# usb_breakout_rev_2.net
KiCad netlist of a schematic drawn in Altium Designer
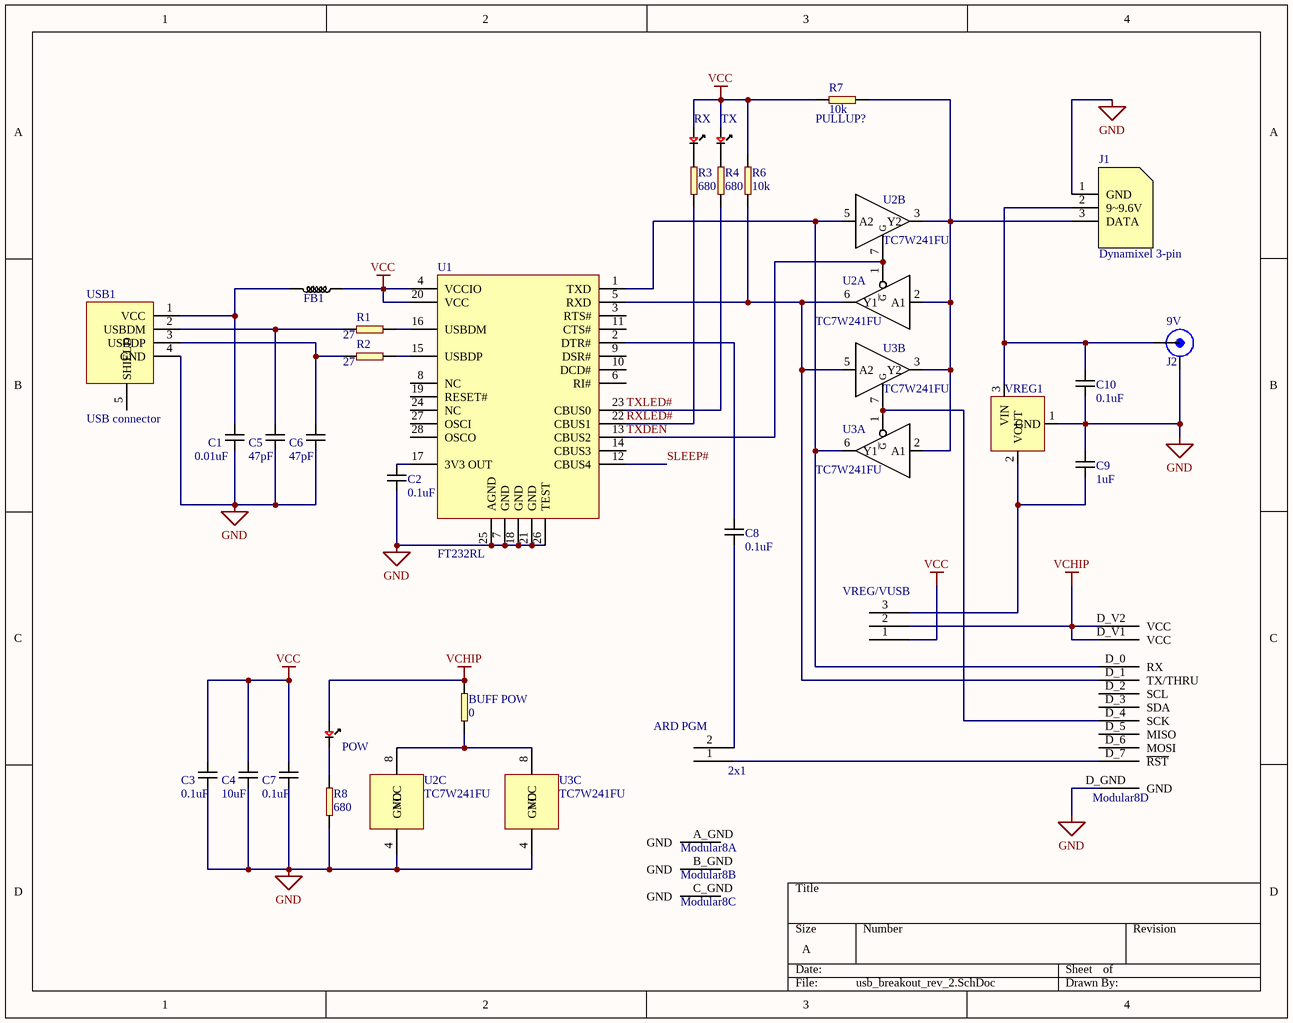
[diagram p0: usb_breakout_rev_2.SchDoc]

(export (version "E")
  (design (tool "Eeschema 10.0.6"))
  (components
    (comp (ref "ARD PGM")
      (value "2x1")
      (footprint "2x1 THRU HOLES 0.1\" PITCH")
      (libsource (lib "OpBots") (part "2x1"))
    )
    (comp (ref "BUFF POW")
      (value "R 0")
      (footprint "0603")
      (fields (field (name "R") "0"))
      (libsource (lib "RLC") (part "R 0"))
    )
    (comp (ref "C1")
      (value "C 0.01uF 25V")
      (footprint "0603")
      (fields (field (name "C") "0.01uF"))
      (libsource (lib "RLC") (part "C 0.01uF 25V"))
    )
    (comp (ref "C2")
      (value "C 0.1uF 25V")
      (footprint "0603")
      (fields (field (name "C") "0.1uF"))
      (libsource (lib "RLC") (part "C 0.1uF 25V"))
    )
    (comp (ref "C3")
      (value "C 0.1uF 25V")
      (footprint "0603")
      (fields (field (name "C") "0.1uF"))
      (libsource (lib "RLC") (part "C 0.1uF 25V"))
    )
    (comp (ref "C4")
      (value "C 10uF 25V")
      (footprint "0603")
      (fields (field (name "C") "10uF"))
      (libsource (lib "RLC") (part "C 10uF 25V"))
    )
    (comp (ref "C5")
      (value "C 47pF 50V")
      (footprint "0603")
      (fields (field (name "C") "47pF"))
      (libsource (lib "RLC") (part "C 47pF 50V"))
    )
    (comp (ref "C6")
      (value "C 47pF 50V")
      (footprint "0603")
      (fields (field (name "C") "47pF"))
      (libsource (lib "RLC") (part "C 47pF 50V"))
    )
    (comp (ref "C7")
      (value "C 0.1uF 25V")
      (footprint "0603")
      (fields (field (name "C") "0.1uF"))
      (libsource (lib "RLC") (part "C 0.1uF 25V"))
    )
    (comp (ref "C8")
      (value "C 0.1uF 25V")
      (footprint "0603")
      (fields (field (name "C") "0.1uF"))
      (libsource (lib "RLC") (part "C 0.1uF 25V"))
    )
    (comp (ref "C9")
      (value "C 1uF 25V")
      (footprint "0603")
      (fields (field (name "C") "1uF"))
      (libsource (lib "RLC") (part "C 1uF 25V"))
    )
    (comp (ref "C10")
      (value "C 0.1uF 25V")
      (footprint "0603")
      (fields (field (name "C") "0.1uF"))
      (libsource (lib "RLC") (part "C 0.1uF 25V"))
    )
    (comp (ref "FB1")
      (value "L Ferrite Bead 600ohm")
      (footprint "0603")
      (libsource (lib "RLC") (part "L Ferrite Bead 600ohm"))
    )
    (comp (ref "J1")
      (value "Dynamixel 3-pin")
      (footprint "DYNAMIXEL 3-PIN")
      (libsource (lib "OpBots") (part "Dynamixel 3-pin"))
    )
    (comp (ref "J2")
      (value "9V")
      (footprint "DC JACK 2.1MM SMT")
      (libsource (lib "OpBots") (part "SMT 2.1MM DC JACK"))
    )
    (comp (ref "Modular8")
      (value "modular8_rev2_D")
      (footprint "modular8 edge D flipped")
      (libsource (lib "OpBots") (part "modular8_rev2_D"))
    )
    (comp (ref "POW") (value "LEDG") (footprint "0805 - LED") (libsource (lib "OpBots") (part "LEDG")))
    (comp (ref "R1")
      (value "R 27")
      (footprint "0603")
      (fields (field (name "R") "27"))
      (libsource (lib "RLC") (part "R 27"))
    )
    (comp (ref "R2")
      (value "R 27")
      (footprint "0603")
      (fields (field (name "R") "27"))
      (libsource (lib "RLC") (part "R 27"))
    )
    (comp (ref "R3")
      (value "R 680")
      (footprint "0603")
      (fields (field (name "R") "680"))
      (libsource (lib "RLC") (part "R 680"))
    )
    (comp (ref "R4")
      (value "R 680")
      (footprint "0603")
      (fields (field (name "R") "680"))
      (libsource (lib "RLC") (part "R 680"))
    )
    (comp (ref "R6")
      (value "R 10k")
      (footprint "0603")
      (fields (field (name "R") "10k"))
      (libsource (lib "RLC") (part "R 10k"))
    )
    (comp (ref "R7")
      (value "PULLUP?")
      (footprint "0603")
      (fields (field (name "R") "10k"))
      (libsource (lib "") (part "R 10k_1"))
    )
    (comp (ref "R8")
      (value "R 680")
      (footprint "0603")
      (fields (field (name "R") "680"))
      (libsource (lib "RLC") (part "R 680"))
    )
    (comp (ref "RX") (value "LEDY") (footprint "0805 - LED") (libsource (lib "OpBots") (part "LEDY")))
    (comp (ref "TX") (value "LEDY") (footprint "0805 - LED") (libsource (lib "OpBots") (part "LEDY")))
    (comp (ref "U1") (value "FT232RL") (footprint "SSOP28") (libsource (lib "OpBots") (part "FT232RL")))
    (comp (ref "U2") (value "TC7W241FU") (footprint "MSOP8") (libsource (lib "") (part "TC7W241FU_1")))
    (comp (ref "U3") (value "TC7W241FU") (footprint "MSOP8") (libsource (lib "") (part "TC7W241FU_1")))
    (comp (ref "USB1")
      (value "USB connector")
      (footprint "USB MINI")
      (libsource (lib "OpBots") (part "USB connector"))
    )
    (comp (ref "VREG/VUSB")
      (value "3x1")
      (footprint "3x1 THRU HOLES 0.1\" PITCH")
      (libsource (lib "OpBots") (part "3x1"))
    )
    (comp (ref "VREG1")
      (value "MCP1754ST 5V REG")
      (footprint "SOT-23-3")
      (libsource (lib "OpBots") (part "MCP1754ST 5V REG"))
    )
  )
  (nets
    (net (code "1") (name "/RXLED#") (class "Default")
      (node (ref "R3") (pin "2") (pintype "passive"))
      (node (ref "U1") (pin "22") (pinfunction "CBUS1_22") (pintype "passive"))
    )
    (net (code "2") (name "/SLEEP#") (class "Default")
      (node (ref "U1") (pin "12") (pinfunction "CBUS4_12") (pintype "passive"))
    )
    (net (code "3") (name "/TXDEN") (class "Default")
      (node (ref "U1") (pin "13") (pinfunction "CBUS2_13") (pintype "passive"))
      (node (ref "U2") (pin "1") (pinfunction "~{G}_1") (pintype "passive"))
      (node (ref "U2") (pin "7") (pinfunction "G_7") (pintype "passive"))
    )
    (net (code "4") (name "/TXLED#") (class "Default")
      (node (ref "R4") (pin "2") (pintype "passive"))
      (node (ref "U1") (pin "23") (pinfunction "CBUS0_23") (pintype "passive"))
    )
    (net (code "5") (name "GND") (class "Default")
      (node (ref "C1") (pin "2") (pintype "passive"))
      (node (ref "C10") (pin "2") (pintype "passive"))
      (node (ref "C2") (pin "2") (pintype "passive"))
      (node (ref "C3") (pin "2") (pintype "passive"))
      (node (ref "C4") (pin "2") (pintype "passive"))
      (node (ref "C5") (pin "2") (pintype "passive"))
      (node (ref "C6") (pin "2") (pintype "passive"))
      (node (ref "C7") (pin "2") (pintype "passive"))
      (node (ref "C9") (pin "1") (pintype "passive"))
      (node (ref "J1") (pin "1") (pinfunction "GND_1") (pintype "passive"))
      (node (ref "J2") (pin "2") (pinfunction "G_2") (pintype "passive"))
      (node (ref "Modular8") (pin "D_GND") (pinfunction "GND_D_GND") (pintype "passive"))
      (node (ref "R8") (pin "2") (pintype "passive"))
      (node (ref "U1") (pin "18") (pinfunction "GND_18") (pintype "passive"))
      (node (ref "U1") (pin "21") (pinfunction "GND_21") (pintype "passive"))
      (node (ref "U1") (pin "25") (pinfunction "AGND_25") (pintype "passive"))
      (node (ref "U1") (pin "26") (pinfunction "TEST_26") (pintype "passive"))
      (node (ref "U1") (pin "7") (pinfunction "GND_7") (pintype "passive"))
      (node (ref "U2") (pin "4") (pinfunction "GND_4") (pintype "passive"))
      (node (ref "U3") (pin "4") (pinfunction "GND_4") (pintype "passive"))
      (node (ref "USB1") (pin "4") (pinfunction "GND_4") (pintype "passive"))
      (node (ref "VREG1") (pin "1") (pinfunction "GND_1") (pintype "passive"))
    )
    (net (code "6") (name "Net-(ARD PGM-Pad2)") (class "Default")
      (node (ref "ARD PGM") (pin "2") (pintype "passive"))
      (node (ref "C8") (pin "2") (pintype "passive"))
    )
    (net (code "7") (name "Net-(J1-9~9.6V)") (class "Default")
      (node (ref "C10") (pin "1") (pintype "passive"))
      (node (ref "J1") (pin "2") (pinfunction "9~9.6V_2") (pintype "passive"))
      (node (ref "J2") (pin "1") (pinfunction "S_1") (pintype "passive"))
      (node (ref "VREG1") (pin "3") (pinfunction "VIN_3") (pintype "passive"))
    )
    (net (code "8") (name "Net-(J1-DATA)") (class "Default")
      (node (ref "J1") (pin "3") (pinfunction "DATA_3") (pintype "passive"))
      (node (ref "R7") (pin "2") (pintype "passive"))
      (node (ref "U2") (pin "2") (pinfunction "A1_2") (pintype "passive"))
      (node (ref "U2") (pin "3") (pinfunction "Y2_3") (pintype "passive"))
      (node (ref "U3") (pin "2") (pinfunction "A1_2") (pintype "passive"))
      (node (ref "U3") (pin "3") (pinfunction "Y2_3") (pintype "passive"))
    )
    (net (code "9") (name "Net-(Modular8D-RX)") (class "Default")
      (node (ref "Modular8") (pin "D_0") (pinfunction "RX_D_0") (pintype "passive"))
      (node (ref "U1") (pin "1") (pinfunction "TXD_1") (pintype "passive"))
      (node (ref "U2") (pin "5") (pinfunction "A2_5") (pintype "passive"))
      (node (ref "U3") (pin "6") (pinfunction "Y1_6") (pintype "passive"))
    )
    (net (code "10") (name "Net-(Modular8D-SCK)") (class "Default")
      (node (ref "Modular8") (pin "D_4") (pinfunction "SCK_D_4") (pintype "passive"))
      (node (ref "U3") (pin "1") (pinfunction "~{G}_1") (pintype "passive"))
      (node (ref "U3") (pin "7") (pinfunction "G_7") (pintype "passive"))
    )
    (net (code "11") (name "Net-(Modular8D-TX{slash}THRU)") (class "Default")
      (node (ref "Modular8") (pin "D_1") (pinfunction "TX/THRU_D_1") (pintype "passive"))
      (node (ref "R6") (pin "2") (pintype "passive"))
      (node (ref "U1") (pin "5") (pinfunction "RXD_5") (pintype "passive"))
      (node (ref "U2") (pin "6") (pinfunction "Y1_6") (pintype "passive"))
      (node (ref "U3") (pin "5") (pinfunction "A2_5") (pintype "passive"))
    )
    (net (code "12") (name "Net-(Modular8D-~{RST})") (class "Default")
      (node (ref "ARD PGM") (pin "1") (pintype "passive"))
      (node (ref "Modular8") (pin "D_7") (pinfunction "~{RST}_D_7") (pintype "passive"))
    )
    (net (code "13") (name "Net-(POW-K)") (class "Default")
      (node (ref "POW") (pin "2") (pinfunction "K_2") (pintype "passive"))
      (node (ref "R8") (pin "1") (pintype "passive"))
    )
    (net (code "14") (name "Net-(RX-K)") (class "Default")
      (node (ref "R3") (pin "1") (pintype "passive"))
      (node (ref "RX") (pin "2") (pinfunction "K_2") (pintype "passive"))
    )
    (net (code "15") (name "Net-(TX-K)") (class "Default")
      (node (ref "R4") (pin "1") (pintype "passive"))
      (node (ref "TX") (pin "2") (pinfunction "K_2") (pintype "passive"))
    )
    (net (code "16") (name "Net-(U1-3V3_OUT)") (class "Default")
      (node (ref "C2") (pin "1") (pintype "passive"))
      (node (ref "U1") (pin "17") (pinfunction "3V3_OUT_17") (pintype "passive"))
    )
    (net (code "17") (name "Net-(U1-DTR#)") (class "Default")
      (node (ref "C8") (pin "1") (pintype "passive"))
      (node (ref "U1") (pin "2") (pinfunction "DTR#_2") (pintype "passive"))
    )
    (net (code "18") (name "Net-(U1-USBDM)") (class "Default")
      (node (ref "R1") (pin "2") (pintype "passive"))
      (node (ref "U1") (pin "16") (pinfunction "USBDM_16") (pintype "passive"))
    )
    (net (code "19") (name "Net-(U1-USBDP)") (class "Default")
      (node (ref "R2") (pin "2") (pintype "passive"))
      (node (ref "U1") (pin "15") (pinfunction "USBDP_15") (pintype "passive"))
    )
    (net (code "20") (name "Net-(U2C-VCC)") (class "Default")
      (node (ref "BUFF POW") (pin "2") (pintype "passive"))
      (node (ref "U2") (pin "8") (pinfunction "VCC_8") (pintype "passive"))
      (node (ref "U3") (pin "8") (pinfunction "VCC_8") (pintype "passive"))
    )
    (net (code "21") (name "Net-(USB1-USBDM)") (class "Default")
      (node (ref "C5") (pin "1") (pintype "passive"))
      (node (ref "R1") (pin "1") (pintype "passive"))
      (node (ref "USB1") (pin "2") (pinfunction "USBDM_2") (pintype "passive"))
    )
    (net (code "22") (name "Net-(USB1-USBDP)") (class "Default")
      (node (ref "C6") (pin "1") (pintype "passive"))
      (node (ref "R2") (pin "1") (pintype "passive"))
      (node (ref "USB1") (pin "3") (pinfunction "USBDP_3") (pintype "passive"))
    )
    (net (code "23") (name "Net-(USB1-VCC)") (class "Default")
      (node (ref "C1") (pin "1") (pintype "passive"))
      (node (ref "FB1") (pin "1") (pintype "passive"))
      (node (ref "USB1") (pin "1") (pinfunction "VCC_1") (pintype "passive"))
    )
    (net (code "24") (name "Net-(VREG1-VOUT)") (class "Default")
      (node (ref "C9") (pin "2") (pintype "passive"))
      (node (ref "VREG/VUSB") (pin "3") (pintype "passive"))
      (node (ref "VREG1") (pin "2") (pinfunction "VOUT_2") (pintype "passive"))
    )
    (net (code "25") (name "VCC") (class "Default")
      (node (ref "C3") (pin "1") (pintype "passive"))
      (node (ref "C4") (pin "1") (pintype "passive"))
      (node (ref "C7") (pin "1") (pintype "passive"))
      (node (ref "FB1") (pin "2") (pintype "passive"))
      (node (ref "R6") (pin "1") (pintype "passive"))
      (node (ref "R7") (pin "1") (pintype "passive"))
      (node (ref "RX") (pin "1") (pinfunction "A_1") (pintype "passive"))
      (node (ref "TX") (pin "1") (pinfunction "A_1") (pintype "passive"))
      (node (ref "U1") (pin "20") (pinfunction "VCC_20") (pintype "passive"))
      (node (ref "U1") (pin "4") (pinfunction "VCCIO_4") (pintype "passive"))
      (node (ref "VREG/VUSB") (pin "1") (pintype "passive"))
    )
    (net (code "26") (name "VCHIP") (class "Default")
      (node (ref "BUFF POW") (pin "1") (pintype "passive"))
      (node (ref "Modular8") (pin "D_V1") (pinfunction "VCC_D_V1") (pintype "passive"))
      (node (ref "Modular8") (pin "D_V2") (pinfunction "VCC_D_V2") (pintype "passive"))
      (node (ref "POW") (pin "1") (pinfunction "A_1") (pintype "passive"))
      (node (ref "VREG/VUSB") (pin "2") (pintype "passive"))
    )
    (net (code "27") (name "unconnected-(Modular8A-GND-PadA_GND)") (class "Default")
      (node (ref "Modular8") (pin "A_GND") (pinfunction "GND_A_GND") (pintype "passive"))
    )
    (net (code "28") (name "unconnected-(Modular8B-GND-PadB_GND)") (class "Default")
      (node (ref "Modular8") (pin "B_GND") (pinfunction "GND_B_GND") (pintype "passive"))
    )
    (net (code "29") (name "unconnected-(Modular8C-GND-PadC_GND)") (class "Default")
      (node (ref "Modular8") (pin "C_GND") (pinfunction "GND_C_GND") (pintype "passive"))
    )
    (net (code "30") (name "unconnected-(Modular8D-MISO-PadD_5)") (class "Default")
      (node (ref "Modular8") (pin "D_5") (pinfunction "MISO_D_5") (pintype "passive"))
    )
    (net (code "31") (name "unconnected-(Modular8D-MOSI-PadD_6)") (class "Default")
      (node (ref "Modular8") (pin "D_6") (pinfunction "MOSI_D_6") (pintype "passive"))
    )
    (net (code "32") (name "unconnected-(Modular8D-SCL-PadD_2)") (class "Default")
      (node (ref "Modular8") (pin "D_2") (pinfunction "SCL_D_2") (pintype "passive"))
    )
    (net (code "33") (name "unconnected-(Modular8D-SDA-PadD_3)") (class "Default")
      (node (ref "Modular8") (pin "D_3") (pinfunction "SDA_D_3") (pintype "passive"))
    )
    (net (code "34") (name "unconnected-(U1-CBUS3-Pad14)") (class "Default")
      (node (ref "U1") (pin "14") (pinfunction "CBUS3_14") (pintype "passive"))
    )
    (net (code "35") (name "unconnected-(U1-CTS#-Pad11)") (class "Default")
      (node (ref "U1") (pin "11") (pinfunction "CTS#_11") (pintype "passive"))
    )
    (net (code "36") (name "unconnected-(U1-DCD#-Pad10)") (class "Default")
      (node (ref "U1") (pin "10") (pinfunction "DCD#_10") (pintype "passive"))
    )
    (net (code "37") (name "unconnected-(U1-DSR#-Pad9)") (class "Default")
      (node (ref "U1") (pin "9") (pinfunction "DSR#_9") (pintype "passive"))
    )
    (net (code "38") (name "unconnected-(U1-NC-Pad8)") (class "Default")
      (node (ref "U1") (pin "8") (pinfunction "NC_8") (pintype "passive"))
    )
    (net (code "39") (name "unconnected-(U1-NC-Pad24)") (class "Default")
      (node (ref "U1") (pin "24") (pinfunction "NC_24") (pintype "passive"))
    )
    (net (code "40") (name "unconnected-(U1-OSCI-Pad27)") (class "Default")
      (node (ref "U1") (pin "27") (pinfunction "OSCI_27") (pintype "passive"))
    )
    (net (code "41") (name "unconnected-(U1-OSCO-Pad28)") (class "Default")
      (node (ref "U1") (pin "28") (pinfunction "OSCO_28") (pintype "passive"))
    )
    (net (code "42") (name "unconnected-(U1-RESET#-Pad19)") (class "Default")
      (node (ref "U1") (pin "19") (pinfunction "RESET#_19") (pintype "passive"))
    )
    (net (code "43") (name "unconnected-(U1-RI#-Pad6)") (class "Default")
      (node (ref "U1") (pin "6") (pinfunction "RI#_6") (pintype "passive"))
    )
    (net (code "44") (name "unconnected-(U1-RTS#-Pad3)") (class "Default")
      (node (ref "U1") (pin "3") (pinfunction "RTS#_3") (pintype "passive"))
    )
    (net (code "45") (name "unconnected-(USB1-SHIELD-Pad5)") (class "Default")
      (node (ref "USB1") (pin "5") (pinfunction "SHIELD_5") (pintype "passive"))
    )
  )
)
